# v1_4.net
KiCad netlist of a schematic drawn in EAGLE
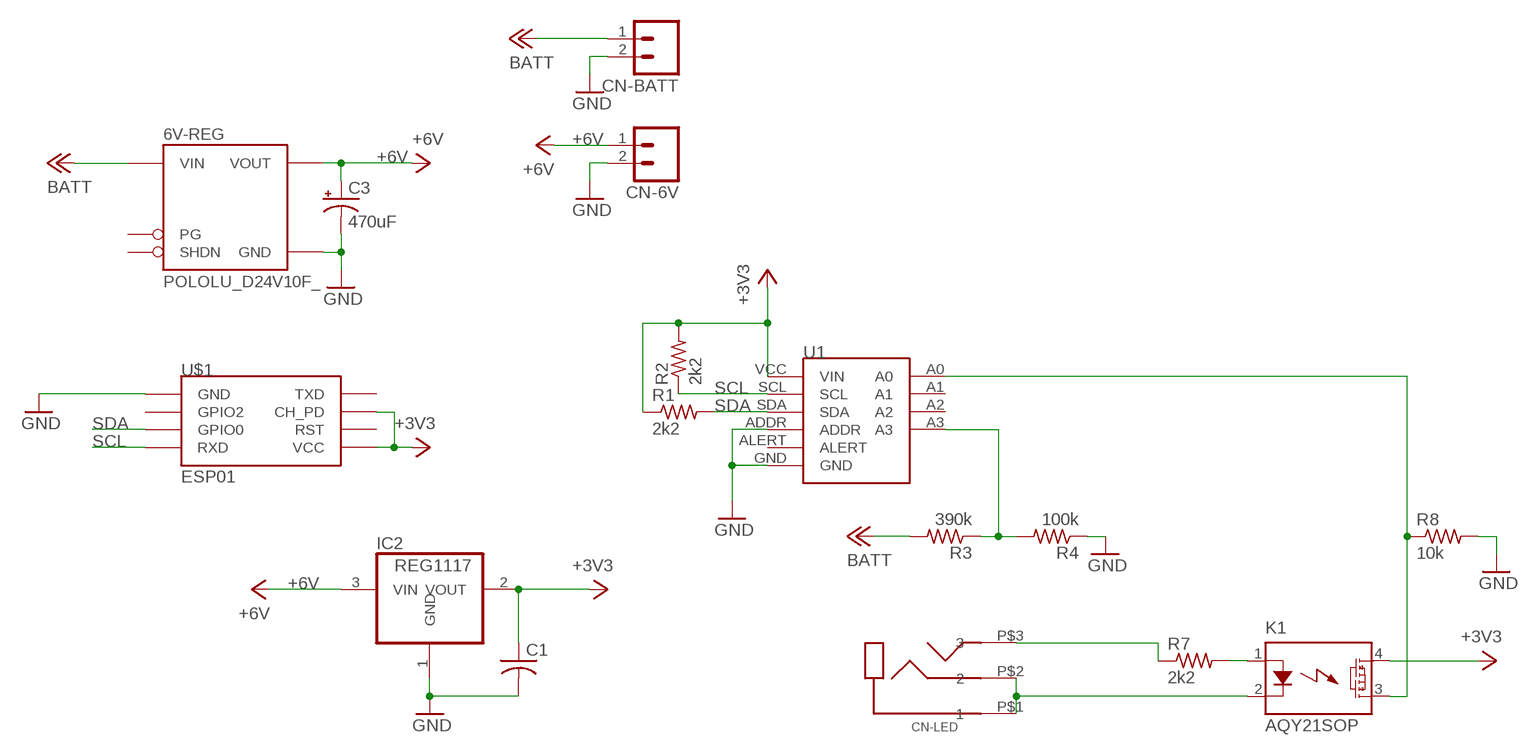
[diagram p0: schematic, sheet 1]

(export (version "E")
  (design (tool "Eeschema 10.0.6"))
  (components
    (comp (ref "6V-REG")
      (value "POLOLU_D24V10F_")
      (footprint "eagle-import:POLOLU_D24V10")
      (libsource (lib "eagle-import") (part "POLOLU_D24V10F_"))
    )
    (comp (ref "C1")
      (value "C-USC1210")
      (footprint "eagle-import:C1210")
      (libsource (lib "eagle-import") (part "C-USC1210"))
    )
    (comp (ref "C3")
      (value "470uF")
      (footprint "eagle-import:CPOL-RADIAL-2.5MM-6.5MM")
      (libsource (lib "eagle-import") (part "100UF-POLAR-RADIAL-2.5MM-25V-20%"))
    )
    (comp (ref "CN-6V")
      (value "M02")
      (footprint "eagle-import:02P")
      (libsource (lib "eagle-import") (part "M02"))
    )
    (comp (ref "CN-BATT")
      (value "M02")
      (footprint "eagle-import:02P")
      (libsource (lib "eagle-import") (part "M02"))
    )
    (comp (ref "CN-LED")
      (value "PJ-320B")
      (footprint "eagle-import:PJ-320B")
      (libsource (lib "eagle-import") (part "PJ-320B"))
    )
    (comp (ref "IC2")
      (value "REG1117")
      (footprint "eagle-import:SOT223")
      (libsource (lib "eagle-import") (part "REG1117"))
    )
    (comp (ref "K1")
      (value "AQY21SOP")
      (footprint "eagle-import:SOP04")
      (libsource (lib "eagle-import") (part "AQYSOP21"))
    )
    (comp (ref "R1")
      (value "2k2")
      (footprint "eagle-import:R0603")
      (libsource (lib "eagle-import") (part "R-US_R0603"))
    )
    (comp (ref "R2")
      (value "2k2")
      (footprint "eagle-import:R0603")
      (libsource (lib "eagle-import") (part "R-US_R0603"))
    )
    (comp (ref "R3")
      (value "390k")
      (footprint "eagle-import:R0603")
      (libsource (lib "eagle-import") (part "R-US_R0603"))
    )
    (comp (ref "R4")
      (value "100k")
      (footprint "eagle-import:R0603")
      (libsource (lib "eagle-import") (part "R-US_R0603"))
    )
    (comp (ref "R7")
      (value "2k2")
      (footprint "eagle-import:R0603")
      (libsource (lib "eagle-import") (part "R-US_R0603"))
    )
    (comp (ref "R8")
      (value "10k")
      (footprint "eagle-import:R0603")
      (libsource (lib "eagle-import") (part "R-US_R0603"))
    )
    (comp (ref "U$1")
      (value "ESP01")
      (footprint "eagle-import:ESP01")
      (libsource (lib "eagle-import") (part "ESP01"))
    )
    (comp (ref "U1")
      (value "GY-ADS1115THM")
      (footprint "eagle-import:GY-ADS1115-THM")
      (libsource (lib "eagle-import") (part "GY-ADS1115THM"))
    )
  )
  (nets
    (net (code "1") (name "+3V3") (class "Default")
      (node (ref "C1") (pin "1") (pinfunction "1_1") (pintype "passive"))
      (node (ref "IC2") (pin "2") (pinfunction "VOUT_2") (pintype "output"))
      (node (ref "K1") (pin "4") (pinfunction "DS1_4") (pintype "passive"))
      (node (ref "R1") (pin "1") (pinfunction "1_1") (pintype "passive"))
      (node (ref "R2") (pin "2") (pinfunction "2_2") (pintype "passive"))
      (node (ref "U$1") (pin "CH_PD") (pinfunction "CH_PD_CH_PD") (pintype "bidirectional"))
      (node (ref "U$1") (pin "VCC") (pinfunction "VCC_VCC") (pintype "bidirectional"))
      (node (ref "U1") (pin "VCC") (pinfunction "VIN_VCC") (pintype "bidirectional"))
    )
    (net (code "2") (name "+6V") (class "Default")
      (node (ref "6V-REG") (pin "VOUT") (pinfunction "VOUT_VOUT") (pintype "output"))
      (node (ref "C3") (pin "1") (pinfunction "+_1") (pintype "passive"))
      (node (ref "CN-6V") (pin "1") (pinfunction "1_1") (pintype "passive"))
      (node (ref "IC2") (pin "3") (pinfunction "VIN_3") (pintype "input"))
    )
    (net (code "3") (name "/SCL") (class "Default")
      (node (ref "R2") (pin "1") (pinfunction "1_1") (pintype "passive"))
      (node (ref "U$1") (pin "RX") (pinfunction "RXD_RX") (pintype "bidirectional"))
      (node (ref "U1") (pin "SCL") (pinfunction "SCL_SCL") (pintype "bidirectional"))
    )
    (net (code "4") (name "/SDA") (class "Default")
      (node (ref "R1") (pin "2") (pinfunction "2_2") (pintype "passive"))
      (node (ref "U$1") (pin "GPIO0") (pinfunction "GPIO0_GPIO0") (pintype "bidirectional"))
      (node (ref "U1") (pin "SDA") (pinfunction "SDA_SDA") (pintype "bidirectional"))
    )
    (net (code "5") (name "BATT") (class "Default")
      (node (ref "6V-REG") (pin "VIN") (pinfunction "VIN_VIN") (pintype "power_in"))
      (node (ref "CN-BATT") (pin "1") (pinfunction "1_1") (pintype "passive"))
      (node (ref "R3") (pin "2") (pinfunction "2_2") (pintype "passive"))
    )
    (net (code "6") (name "GND") (class "Default")
      (node (ref "6V-REG") (pin "GND") (pinfunction "GND_GND") (pintype "power_in"))
      (node (ref "C1") (pin "2") (pinfunction "2_2") (pintype "passive"))
      (node (ref "C3") (pin "2") (pinfunction "-_2") (pintype "passive"))
      (node (ref "CN-6V") (pin "2") (pinfunction "2_2") (pintype "passive"))
      (node (ref "CN-BATT") (pin "2") (pinfunction "2_2") (pintype "passive"))
      (node (ref "IC2") (pin "1") (pinfunction "GND_1") (pintype "power_in"))
      (node (ref "R4") (pin "1") (pinfunction "1_1") (pintype "passive"))
      (node (ref "R8") (pin "2") (pinfunction "2_2") (pintype "passive"))
      (node (ref "U$1") (pin "GND") (pinfunction "GND_GND") (pintype "bidirectional"))
      (node (ref "U1") (pin "ADDR") (pinfunction "ADDR_ADDR") (pintype "bidirectional"))
      (node (ref "U1") (pin "GND") (pinfunction "GND_GND") (pintype "bidirectional"))
    )
    (net (code "7") (name "Net-(CN-LED-1)") (class "Default")
      (node (ref "CN-LED") (pin "P$1") (pinfunction "1_P$1") (pintype "bidirectional"))
      (node (ref "CN-LED") (pin "P$2") (pinfunction "2_P$2") (pintype "bidirectional"))
      (node (ref "K1") (pin "2") (pinfunction "K_2") (pintype "passive"))
    )
    (net (code "8") (name "Net-(CN-LED-3)") (class "Default")
      (node (ref "CN-LED") (pin "P$3") (pinfunction "3_P$3") (pintype "bidirectional"))
      (node (ref "R7") (pin "1") (pinfunction "1_1") (pintype "passive"))
    )
    (net (code "9") (name "Net-(K1-A)") (class "Default")
      (node (ref "K1") (pin "1") (pinfunction "A_1") (pintype "passive"))
      (node (ref "R7") (pin "2") (pinfunction "2_2") (pintype "passive"))
    )
    (net (code "10") (name "Net-(K1-DS2)") (class "Default")
      (node (ref "K1") (pin "3") (pinfunction "DS2_3") (pintype "passive"))
      (node (ref "R8") (pin "1") (pinfunction "1_1") (pintype "passive"))
      (node (ref "U1") (pin "A0") (pinfunction "A0_A0") (pintype "bidirectional"))
    )
    (net (code "11") (name "Net-(R3-Pad1)") (class "Default")
      (node (ref "R3") (pin "1") (pinfunction "1_1") (pintype "passive"))
      (node (ref "R4") (pin "2") (pinfunction "2_2") (pintype "passive"))
      (node (ref "U1") (pin "A3") (pinfunction "A3_A3") (pintype "bidirectional"))
    )
    (net (code "12") (name "unconnected-(6V-REG-PadPG)") (class "Default")
      (node (ref "6V-REG") (pin "PG") (pinfunction "PG_PG") (pintype "output"))
    )
    (net (code "13") (name "unconnected-(6V-REG-PadSHDN)") (class "Default")
      (node (ref "6V-REG") (pin "SHDN") (pinfunction "SHDN_SHDN") (pintype "input"))
    )
    (net (code "14") (name "unconnected-(U$1-PadGPIO2)") (class "Default")
      (node (ref "U$1") (pin "GPIO2") (pinfunction "GPIO2_GPIO2") (pintype "bidirectional"))
    )
    (net (code "15") (name "unconnected-(U$1-PadRST)") (class "Default")
      (node (ref "U$1") (pin "RST") (pinfunction "RST_RST") (pintype "bidirectional"))
    )
    (net (code "16") (name "unconnected-(U$1-TXD-PadTX)") (class "Default")
      (node (ref "U$1") (pin "TX") (pinfunction "TXD_TX") (pintype "bidirectional"))
    )
    (net (code "17") (name "unconnected-(U1-PadA1)") (class "Default")
      (node (ref "U1") (pin "A1") (pinfunction "A1_A1") (pintype "bidirectional"))
    )
    (net (code "18") (name "unconnected-(U1-PadA2)") (class "Default")
      (node (ref "U1") (pin "A2") (pinfunction "A2_A2") (pintype "bidirectional"))
    )
    (net (code "19") (name "unconnected-(U1-PadALERT)") (class "Default")
      (node (ref "U1") (pin "ALERT") (pinfunction "ALERT_ALERT") (pintype "bidirectional"))
    )
  )
)
